# PCB.net
KiCad netlist of a schematic drawn in EAGLE
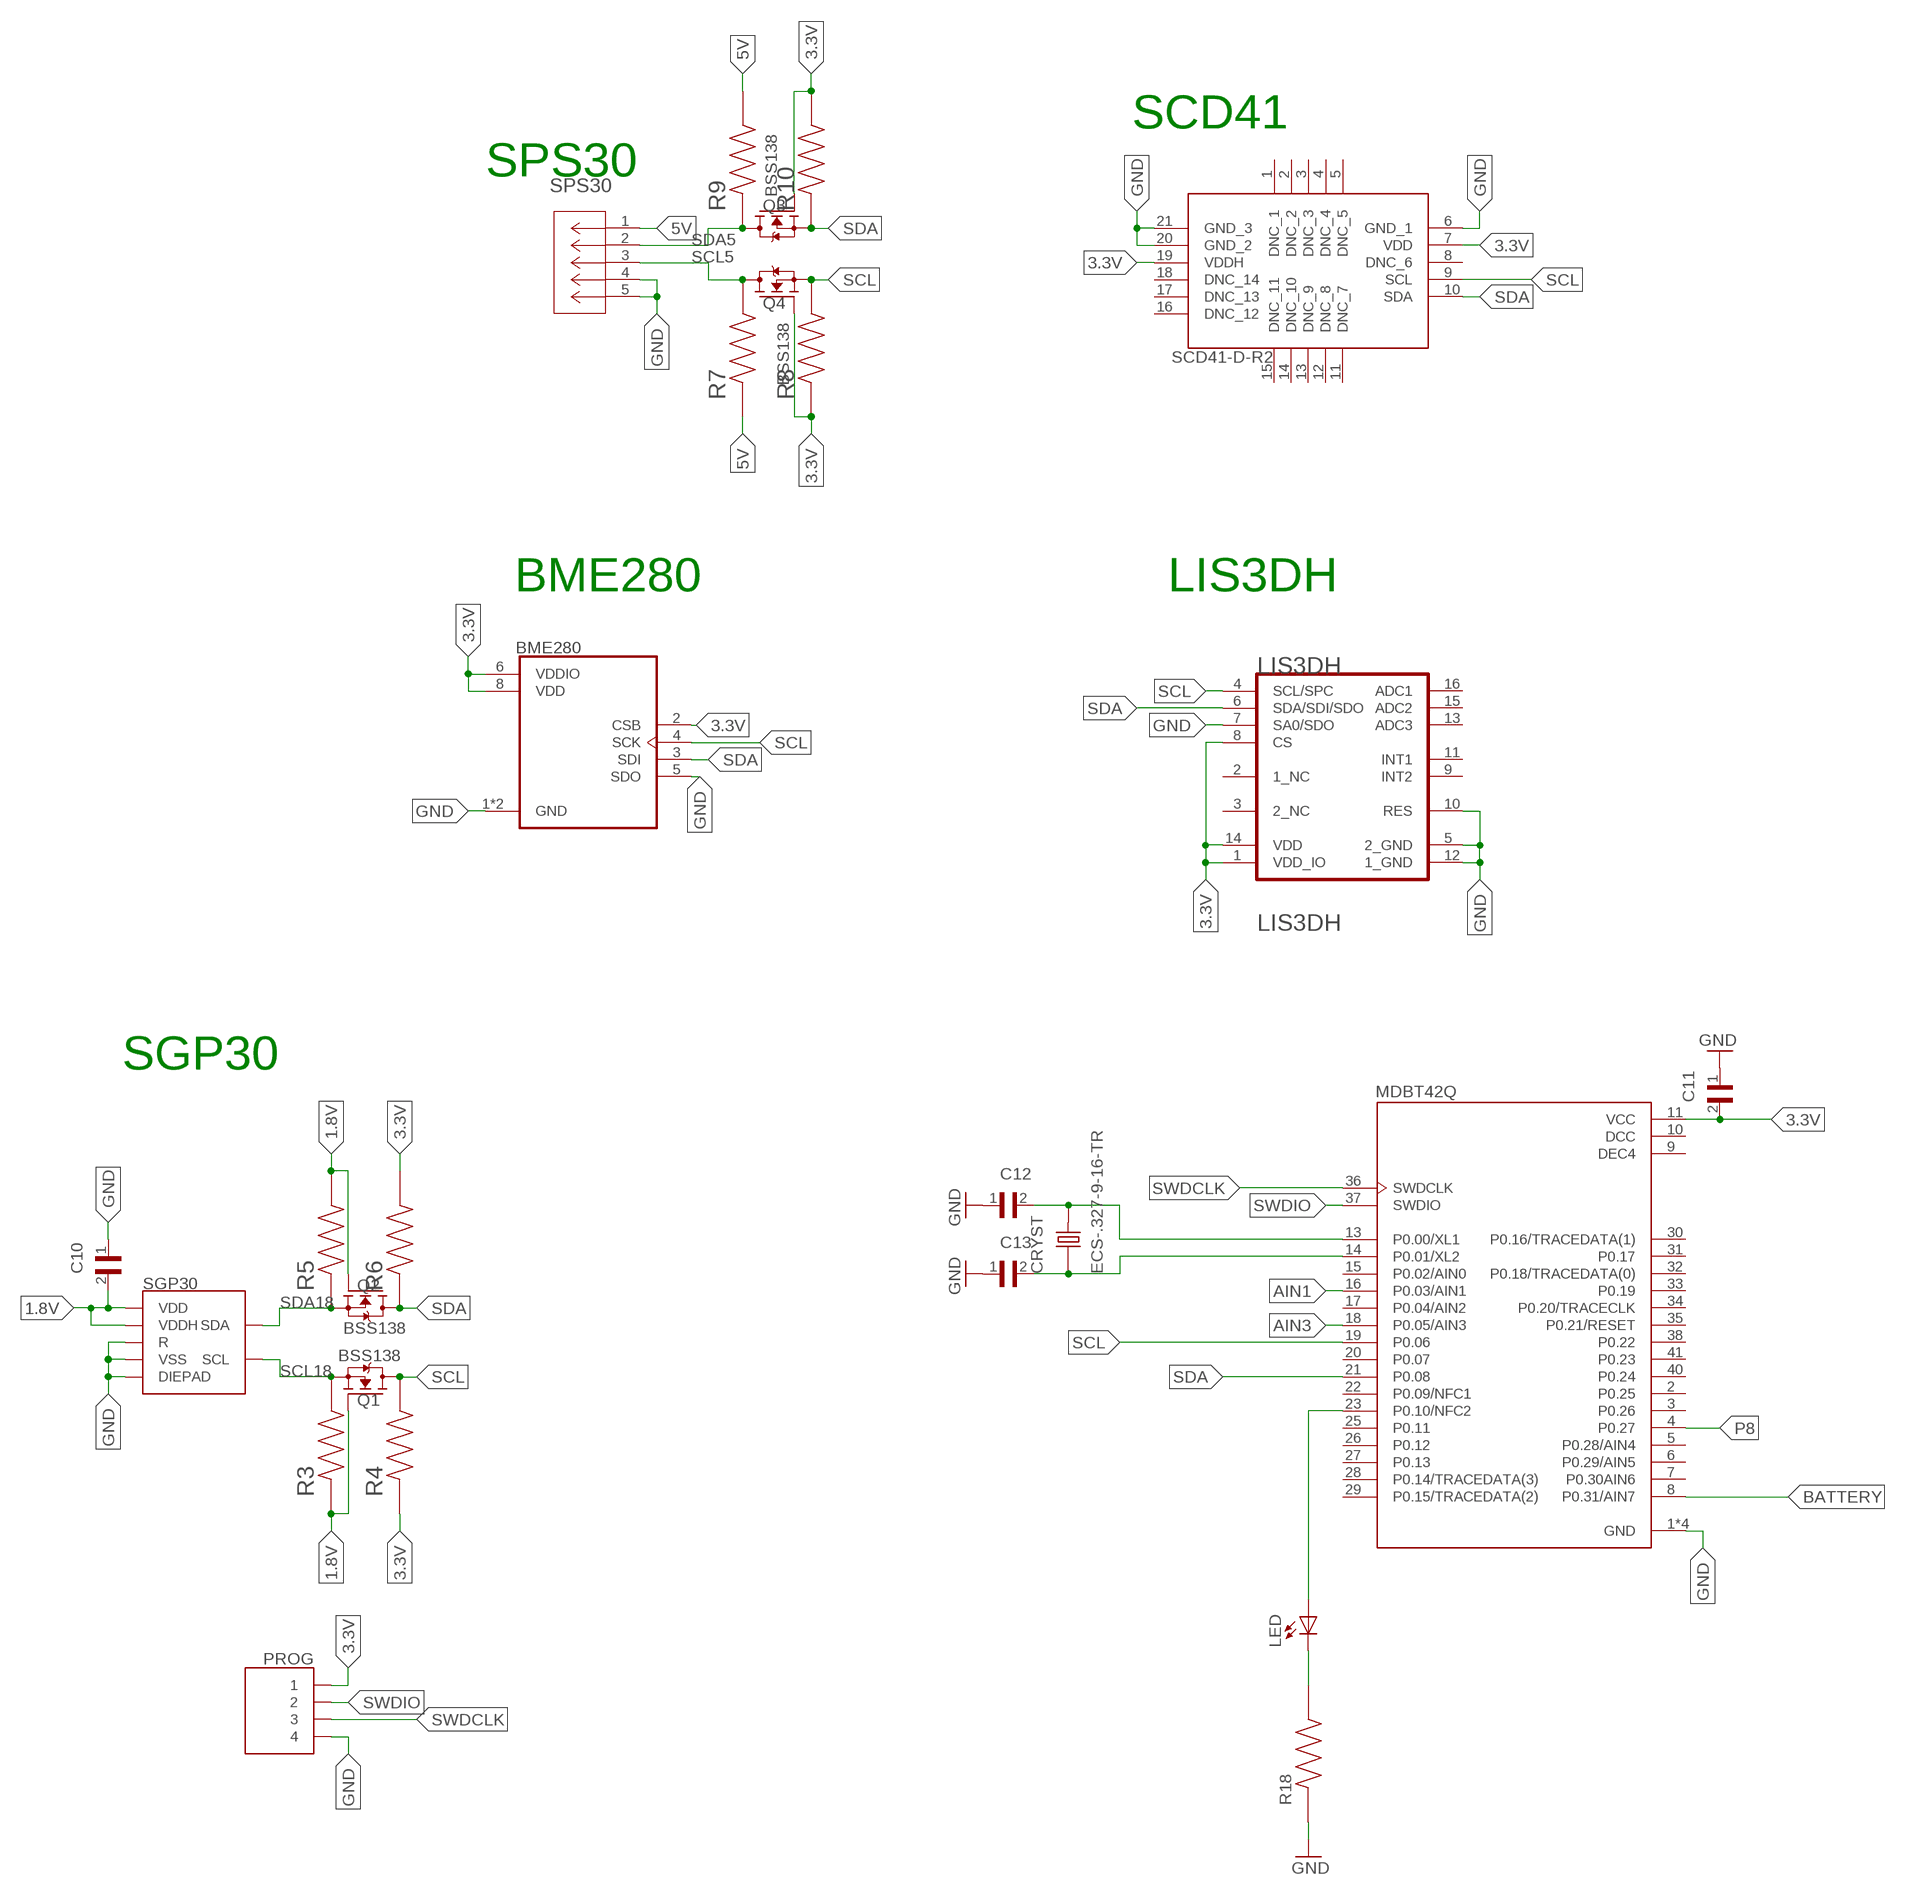
[diagram p0: schematic, sheet 1, part 1 of 2]
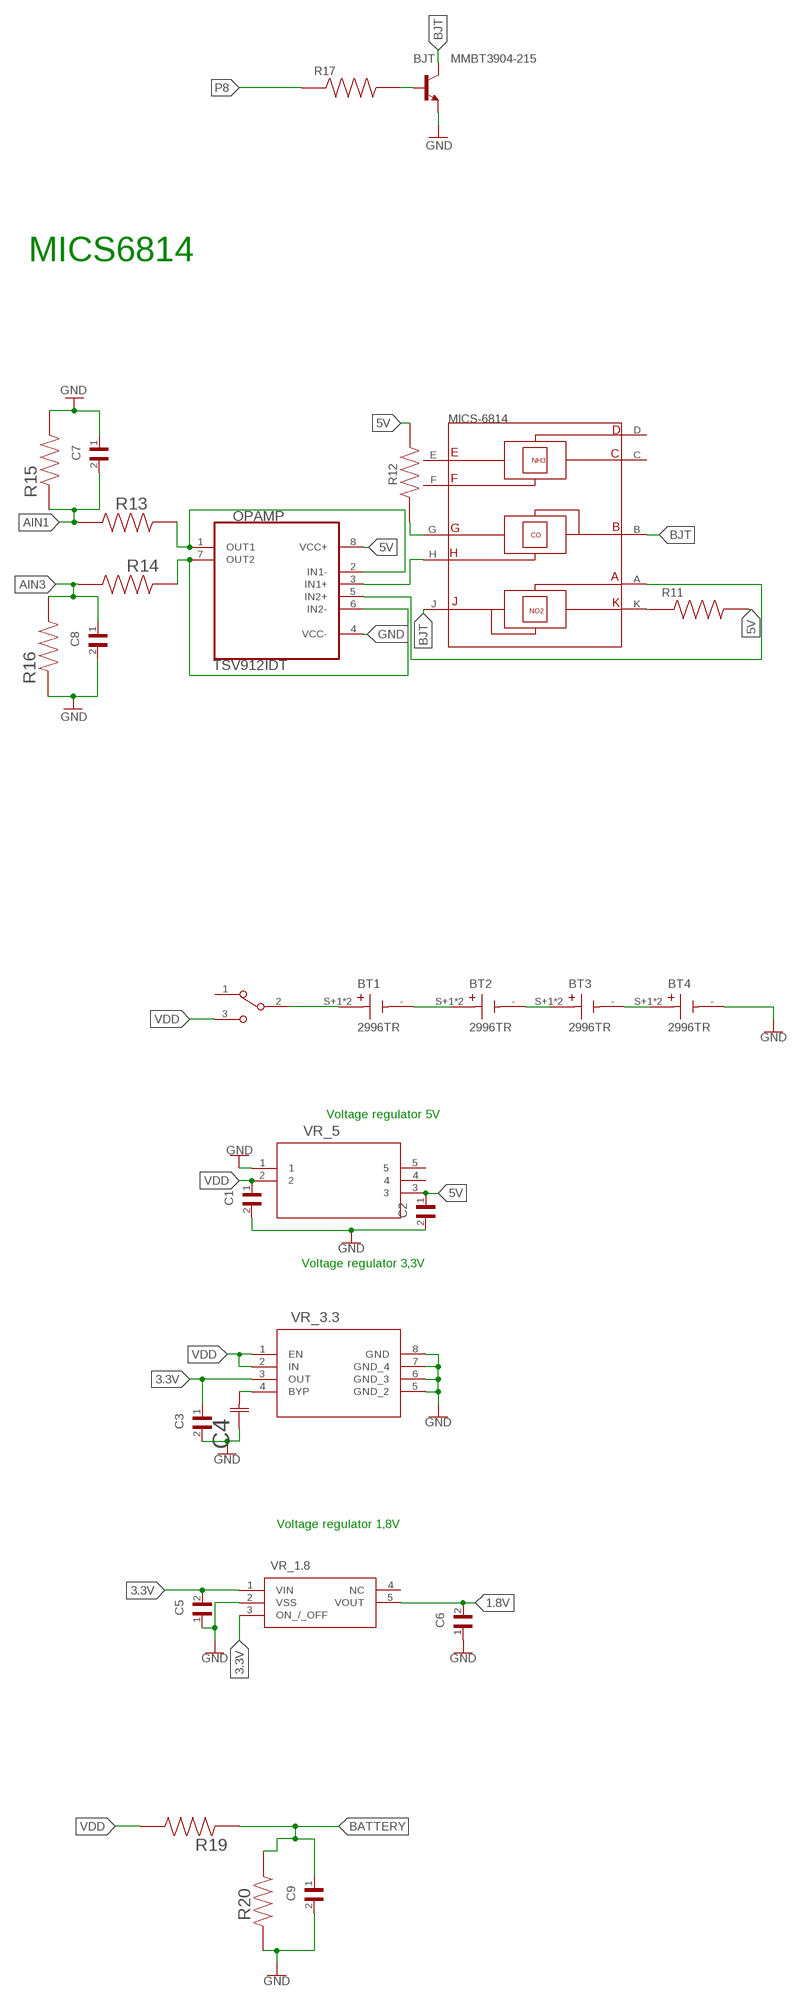
[diagram p1: schematic, sheet 1, part 2 of 2]

(export (version "E")
  (design (tool "Eeschema 10.0.6"))
  (components
    (comp (ref "BJT")
      (value "MMBT3904-215")
      (footprint "eagle-import:SOT95P230X110-3N")
      (fields
        (field (name "DIGI-KEY_PART_NUMBER") "1727-4044-2-ND")
        (field (name "MF") "Nexperia USA")
        (field (name "MP") "MMBT3904,215")
      )
      (libsource (lib "eagle-import") (part "MMBT3904-215"))
    )
    (comp (ref "BME280")
      (value "BME280")
      (footprint "eagle-import:PSON65P250X250X100-8N")
      (fields (field (name "MF") "Bosch"))
      (libsource (lib "eagle-import") (part "BME280"))
    )
    (comp (ref "BT1")
      (value "2996TR")
      (footprint "eagle-import:BAT_2996TR")
      (fields (field (name "DIGI-KEY_PART_NUMBER") "36-2996TR-ND") (field (name "MF") "Keystone Electronics"))
      (libsource (lib "eagle-import") (part "2996TR"))
    )
    (comp (ref "BT2")
      (value "2996TR")
      (footprint "eagle-import:BAT_2996TR")
      (fields (field (name "DIGI-KEY_PART_NUMBER") "36-2996TR-ND") (field (name "MF") "Keystone Electronics"))
      (libsource (lib "eagle-import") (part "2996TR"))
    )
    (comp (ref "BT3")
      (value "2996TR")
      (footprint "eagle-import:BAT_2996TR")
      (fields (field (name "DIGI-KEY_PART_NUMBER") "36-2996TR-ND") (field (name "MF") "Keystone Electronics"))
      (libsource (lib "eagle-import") (part "2996TR"))
    )
    (comp (ref "BT4")
      (value "2996TR")
      (footprint "eagle-import:BAT_2996TR")
      (fields (field (name "DIGI-KEY_PART_NUMBER") "36-2996TR-ND") (field (name "MF") "Keystone Electronics"))
      (libsource (lib "eagle-import") (part "2996TR"))
    )
    (comp (ref "C1")
      (value "C0402C104K9RACAUTO")
      (footprint "eagle-import:CAPC1005X55N")
      (fields (field (name "DIGI-KEY_PART_NUMBER") "399-19367-2-ND") (field (name "MF") "KEMET"))
      (libsource (lib "eagle-import") (part "C0402C104K9RACAUTO"))
    )
    (comp (ref "C2")
      (value "C0402C104K9RACAUTO")
      (footprint "eagle-import:CAPC1005X55N")
      (fields (field (name "DIGI-KEY_PART_NUMBER") "399-19367-2-ND") (field (name "MF") "KEMET"))
      (libsource (lib "eagle-import") (part "C0402C104K9RACAUTO"))
    )
    (comp (ref "C3")
      (value "CL05A225MQ5NNNC")
      (footprint "eagle-import:CAPC1005X55N")
      (fields (field (name "DIGI-KEY_PART_NUMBER") "1276-1469-2-ND") (field (name "MF") "Samsung"))
      (libsource (lib "eagle-import") (part "CL05A225MQ5NNNC"))
    )
    (comp (ref "C4")
      (value "CL05B471KB5NNNCCAP_CL05_SAM")
      (footprint "eagle-import:CAP_CL05_SAM")
      (fields
        (field (name "MANUFACTURER_PART_NUMBER") "CL05B471KB5NNNC")
        (field (name "COPYRIGHT") "Copyright (C) 2022 Ultra Librarian. All rights reserved.")
      )
      (libsource (lib "eagle-import") (part "CL05B471KB5NNNCCAP_CL05_SAM"))
    )
    (comp (ref "C5")
      (value "JMK105BJ105KV-F")
      (footprint "eagle-import:CAPC1005X55N")
      (fields (field (name "DIGI-KEY_PART_NUMBER") "587-1231-2-ND") (field (name "MF") "Taiyo Yuden"))
      (libsource (lib "eagle-import") (part "JMK105BJ105KV-F"))
    )
    (comp (ref "C6")
      (value "JMK105BJ105KV-F")
      (footprint "eagle-import:CAPC1005X55N")
      (fields (field (name "DIGI-KEY_PART_NUMBER") "587-1231-2-ND") (field (name "MF") "Taiyo Yuden"))
      (libsource (lib "eagle-import") (part "JMK105BJ105KV-F"))
    )
    (comp (ref "C7")
      (value "CL05B103KO5NNNC")
      (footprint "eagle-import:CAPC1005X55N")
      (fields
        (field (name "DIGI-KEY_PART_NUMBER") "1276-1051-2-ND")
        (field (name "MF") "Samsung Electro-Mechanics")
      )
      (libsource (lib "eagle-import") (part "CL05B103KO5NNNC"))
    )
    (comp (ref "C8")
      (value "CL05B103KO5NNNC")
      (footprint "eagle-import:CAPC1005X55N")
      (fields
        (field (name "DIGI-KEY_PART_NUMBER") "1276-1051-2-ND")
        (field (name "MF") "Samsung Electro-Mechanics")
      )
      (libsource (lib "eagle-import") (part "CL05B103KO5NNNC"))
    )
    (comp (ref "C9")
      (value "CL05B103KO5NNNC")
      (footprint "eagle-import:CAPC1005X55N")
      (fields
        (field (name "DIGI-KEY_PART_NUMBER") "1276-1051-2-ND")
        (field (name "MF") "Samsung Electro-Mechanics")
      )
      (libsource (lib "eagle-import") (part "CL05B103KO5NNNC"))
    )
    (comp (ref "C10")
      (value "C0402C104K9RACAUTO")
      (footprint "eagle-import:CAPC1005X55N")
      (fields (field (name "DIGI-KEY_PART_NUMBER") "399-19367-2-ND") (field (name "MF") "KEMET"))
      (libsource (lib "eagle-import") (part "C0402C104K9RACAUTO"))
    )
    (comp (ref "C11")
      (value "CL05A106MP5NUNC")
      (footprint "eagle-import:CAPC1005X55N")
      (fields (field (name "DIGI-KEY_PART_NUMBER") "1276-1450-2-ND") (field (name "MF") "Samsung"))
      (libsource (lib "eagle-import") (part "CL05A106MP5NUNC"))
    )
    (comp (ref "C12")
      (value "04025A120FAT2A")
      (footprint "eagle-import:CAPC1005X56N")
      (fields (field (name "DIGI-KEY_PART_NUMBER") "478-10087-2-ND") (field (name "MF") "AVX"))
      (libsource (lib "eagle-import") (part "04025A120FAT2A"))
    )
    (comp (ref "C13")
      (value "04025A120FAT2A")
      (footprint "eagle-import:CAPC1005X56N")
      (fields (field (name "DIGI-KEY_PART_NUMBER") "478-10087-2-ND") (field (name "MF") "AVX"))
      (libsource (lib "eagle-import") (part "04025A120FAT2A"))
    )
    (comp (ref "CRYST")
      (value "ECS-.327-9-16-TR")
      (footprint "eagle-import:XTAL_ECS-.327-9-16-TR")
      (fields (field (name "DIGI-KEY_PART_NUMBER") "XC2132TR-ND") (field (name "MF") "ECS Inc."))
      (libsource (lib "eagle-import") (part "ECS-.327-9-16-TR"))
    )
    (comp (ref "LED")
      (value "LTST-C170KRKT")
      (footprint "eagle-import:DIOC200X125X110")
      (fields (field (name "DIGI-KEY_PART_NUMBER") "160-1415-2-ND") (field (name "MF") "Lite-On Inc."))
      (libsource (lib "eagle-import") (part "LTST-C170KRKT"))
    )
    (comp (ref "LIS3DH")
      (value "STMICROELECTRONICS_LIS3DHSTMICROELECTRONICS_LIS3DH_0_0")
      (footprint "eagle-import:STMICROELECTRONICS_LIS3DH_0")
      (fields (field (name "MF") "STMicroelectronics") (field (name "MPN") "LIS3DH"))
      (libsource (lib "eagle-import") (part "STMICROELECTRONICS_LIS3DHSTMICROELECTRONICS_LIS3DH_0_0"))
    )
    (comp (ref "MDBT42Q")
      (value "317030213")
      (footprint "eagle-import:XCVR_317030213")
      (fields (field (name "DIGI-KEY_PART_NUMBER") "1597-1434-ND") (field (name "MF") "Seeed Technology"))
      (libsource (lib "eagle-import") (part "317030213"))
    )
    (comp (ref "MICS6814")
      (value "MICS-6814")
      (footprint "eagle-import:SENSOR_MICS-6814")
      (fields (field (name "MF") "MikroElektronika"))
      (libsource (lib "eagle-import") (part "MICS-6814"))
    )
    (comp (ref "OPAMP")
      (value "TSV912IDT")
      (footprint "eagle-import:SOIC127P600X175-8N")
      (fields (field (name "MF") "STMicroelectronics"))
      (libsource (lib "eagle-import") (part "TSV912IDT"))
    )
    (comp (ref "PROG")
      (value "BG306-04-A-1-0400-X-X_REVD")
      (footprint "eagle-import:GCT_BG306-04-A-1-0400-X-X_REVD")
      (fields
        (field (name "DIGI-KEY_PART_NUMBER") "2073-BG306-04-A-1-0400-L-BTR-ND")
        (field (name "MF") "Global Connector Technology")
        (field (name "MP") "BG306-04-A-1-0400-L-B")
      )
      (libsource (lib "eagle-import") (part "BG306-04-A-1-0400-X-X_REVD"))
    )
    (comp (ref "Q1")
      (value "BSS138")
      (footprint "eagle-import:SOT95P240X111-3N")
      (fields (field (name "DIGI-KEY_PART_NUMBER") "BSS138TR-ND") (field (name "MF") "ON Semiconductor"))
      (libsource (lib "eagle-import") (part "BSS138"))
    )
    (comp (ref "Q2")
      (value "BSS138")
      (footprint "eagle-import:SOT95P240X111-3N")
      (fields (field (name "DIGI-KEY_PART_NUMBER") "BSS138TR-ND") (field (name "MF") "ON Semiconductor"))
      (libsource (lib "eagle-import") (part "BSS138"))
    )
    (comp (ref "Q3")
      (value "BSS138")
      (footprint "eagle-import:SOT95P240X111-3N")
      (fields (field (name "DIGI-KEY_PART_NUMBER") "BSS138TR-ND") (field (name "MF") "ON Semiconductor"))
      (libsource (lib "eagle-import") (part "BSS138"))
    )
    (comp (ref "Q4")
      (value "BSS138")
      (footprint "eagle-import:SOT95P240X111-3N")
      (fields (field (name "DIGI-KEY_PART_NUMBER") "BSS138TR-ND") (field (name "MF") "ON Semiconductor"))
      (libsource (lib "eagle-import") (part "BSS138"))
    )
    (comp (ref "R3")
      (value "MCS0402MC1002FE000")
      (footprint "eagle-import:RESC1005X37N")
      (fields
        (field (name "DIGI-KEY_PART_NUMBER") "MCS0402-10.0K-MFTR-ND")
        (field (name "MF") "Vishay Beyschlag")
      )
      (libsource (lib "eagle-import") (part "MCS0402MC1002FE000"))
    )
    (comp (ref "R4")
      (value "MCS0402MC1002FE000")
      (footprint "eagle-import:RESC1005X37N")
      (fields
        (field (name "DIGI-KEY_PART_NUMBER") "MCS0402-10.0K-MFTR-ND")
        (field (name "MF") "Vishay Beyschlag")
      )
      (libsource (lib "eagle-import") (part "MCS0402MC1002FE000"))
    )
    (comp (ref "R5")
      (value "MCS0402MC1002FE000")
      (footprint "eagle-import:RESC1005X37N")
      (fields
        (field (name "DIGI-KEY_PART_NUMBER") "MCS0402-10.0K-MFTR-ND")
        (field (name "MF") "Vishay Beyschlag")
      )
      (libsource (lib "eagle-import") (part "MCS0402MC1002FE000"))
    )
    (comp (ref "R6")
      (value "MCS0402MC1002FE000")
      (footprint "eagle-import:RESC1005X37N")
      (fields
        (field (name "DIGI-KEY_PART_NUMBER") "MCS0402-10.0K-MFTR-ND")
        (field (name "MF") "Vishay Beyschlag")
      )
      (libsource (lib "eagle-import") (part "MCS0402MC1002FE000"))
    )
    (comp (ref "R7")
      (value "MCS0402MC1002FE000")
      (footprint "eagle-import:RESC1005X37N")
      (fields
        (field (name "DIGI-KEY_PART_NUMBER") "MCS0402-10.0K-MFTR-ND")
        (field (name "MF") "Vishay Beyschlag")
      )
      (libsource (lib "eagle-import") (part "MCS0402MC1002FE000"))
    )
    (comp (ref "R8")
      (value "MCS0402MC1002FE000")
      (footprint "eagle-import:RESC1005X37N")
      (fields
        (field (name "DIGI-KEY_PART_NUMBER") "MCS0402-10.0K-MFTR-ND")
        (field (name "MF") "Vishay Beyschlag")
      )
      (libsource (lib "eagle-import") (part "MCS0402MC1002FE000"))
    )
    (comp (ref "R9")
      (value "MCS0402MC1002FE000")
      (footprint "eagle-import:RESC1005X37N")
      (fields
        (field (name "DIGI-KEY_PART_NUMBER") "MCS0402-10.0K-MFTR-ND")
        (field (name "MF") "Vishay Beyschlag")
      )
      (libsource (lib "eagle-import") (part "MCS0402MC1002FE000"))
    )
    (comp (ref "R10")
      (value "MCS0402MC1002FE000")
      (footprint "eagle-import:RESC1005X37N")
      (fields
        (field (name "DIGI-KEY_PART_NUMBER") "MCS0402-10.0K-MFTR-ND")
        (field (name "MF") "Vishay Beyschlag")
      )
      (libsource (lib "eagle-import") (part "MCS0402MC1002FE000"))
    )
    (comp (ref "R11")
      (value "ERJPA2F1300X")
      (footprint "eagle-import:RES_ERJPA2F1300X")
      (fields (field (name "DIGI-KEY_PART_NUMBER") "P124437TR-ND") (field (name "MF") "Panasonic"))
      (libsource (lib "eagle-import") (part "ERJPA2F1300X"))
    )
    (comp (ref "R12")
      (value "ERJPA2J821X")
      (footprint "eagle-import:RES_ERJPA2J821X")
      (fields (field (name "DIGI-KEY_PART_NUMBER") "P124598TR-ND") (field (name "MF") "Panasonic"))
      (libsource (lib "eagle-import") (part "ERJPA2J821X"))
    )
    (comp (ref "R13")
      (value "ERJ-2GEJ515X")
      (footprint "eagle-import:RESC1005X40N")
      (fields (field (name "DIGI-KEY_PART_NUMBER") "P5.1MJTR-ND") (field (name "MF") "Panasonic"))
      (libsource (lib "eagle-import") (part "ERJ-2GEJ515X"))
    )
    (comp (ref "R14")
      (value "ERJ-2GEJ515X")
      (footprint "eagle-import:RESC1005X40N")
      (fields (field (name "DIGI-KEY_PART_NUMBER") "P5.1MJTR-ND") (field (name "MF") "Panasonic"))
      (libsource (lib "eagle-import") (part "ERJ-2GEJ515X"))
    )
    (comp (ref "R15")
      (value "ERJ-2GEJ106X")
      (footprint "eagle-import:RESC1005X40N")
      (fields (field (name "DIGI-KEY_PART_NUMBER") "P10MJTR-ND") (field (name "MF") "Panasonic Electronic"))
      (libsource (lib "eagle-import") (part "ERJ-2GEJ106X"))
    )
    (comp (ref "R16")
      (value "ERJ-2GEJ106X")
      (footprint "eagle-import:RESC1005X40N")
      (fields (field (name "DIGI-KEY_PART_NUMBER") "P10MJTR-ND") (field (name "MF") "Panasonic Electronic"))
      (libsource (lib "eagle-import") (part "ERJ-2GEJ106X"))
    )
    (comp (ref "R17")
      (value "ERJPA2F5101X")
      (footprint "eagle-import:RES_ERJPA2F5101X")
      (fields (field (name "DIGI-KEY_PART_NUMBER") "P124488TR-ND") (field (name "MF") "Panasonic"))
      (libsource (lib "eagle-import") (part "ERJPA2F5101X"))
    )
    (comp (ref "R18")
      (value "ERA2AEB331X")
      (footprint "eagle-import:RES_ERA2AEB331X")
      (fields (field (name "DIGI-KEY_PART_NUMBER") "P330DCTR-ND") (field (name "MF") "Panasonic"))
      (libsource (lib "eagle-import") (part "ERA2AEB331X"))
    )
    (comp (ref "R19")
      (value "ERJ-2GEJ106X")
      (footprint "eagle-import:RESC1005X40N")
      (fields (field (name "DIGI-KEY_PART_NUMBER") "P10MJTR-ND") (field (name "MF") "Panasonic Electronic"))
      (libsource (lib "eagle-import") (part "ERJ-2GEJ106X"))
    )
    (comp (ref "R20")
      (value "ERJ-2GEJ106X")
      (footprint "eagle-import:RESC1005X40N")
      (fields (field (name "DIGI-KEY_PART_NUMBER") "P10MJTR-ND") (field (name "MF") "Panasonic Electronic"))
      (libsource (lib "eagle-import") (part "ERJ-2GEJ106X"))
    )
    (comp (ref "S1")
      (value "EG1213")
      (footprint "eagle-import:SW_EG1213")
      (fields (field (name "DIGI-KEY_PART_NUMBER") "EG1906-ND") (field (name "MF") "E-Switch"))
      (libsource (lib "eagle-import") (part "EG1213"))
    )
    (comp (ref "SCD41")
      (value "SCD41-D-R2")
      (footprint "eagle-import:SCD41DR2")
      (fields (field (name "MOUSER_PART_NUMBER") "403-SCD41-D-R2"))
      (libsource (lib "eagle-import") (part "SCD41-D-R2"))
    )
    (comp (ref "SGP30")
      (value "SGP30")
      (footprint "eagle-import:SGP30")
      (fields (field (name "MF") "Sensirion AG"))
      (libsource (lib "eagle-import") (part "SGP30"))
    )
    (comp (ref "SPS30")
      (value "S5B-ZR-SM4A-TF_(LF)_(SN)CONN_S5B-ZR-SM4A-TF_JST")
      (footprint "eagle-import:CONN_S5B-ZR-SM4A-TF_JST")
      (fields
        (field (name "MANUFACTURER_PART_NUMBER") "S5B-ZR-SM4A-TF (LF) (SN)")
        (field (name "COPYRIGHT") "Copyright (C) 2022 Ultra Librarian. All rights reserved.")
      )
      (libsource (lib "eagle-import") (part "S5B-ZR-SM4A-TF_(LF)_(SN)CONN_S5B-ZR-SM4A-TF_JST"))
    )
    (comp (ref "VR_1.8")
      (value "S-1318D18-M5T1U4")
      (footprint "eagle-import:SOT95P275X130-5N")
      (fields (field (name "MOUSER_PART_NUMBER") "628-S-1318D18-M5T1U4"))
      (libsource (lib "eagle-import") (part "S-1318D18-M5T1U4"))
    )
    (comp (ref "VR_3.3")
      (value "MIC5219-3.3YMMMSOP-8LD-PL-1_MCH")
      (footprint "eagle-import:MSOP-8LD-PL-1_MCH")
      (fields
        (field (name "MANUFACTURER_PART_NUMBER") "MIC5219-3.3YMM")
        (field (name "COPYRIGHT") "Copyright (C) 2022 Ultra Librarian. All rights reserved.")
      )
      (libsource (lib "eagle-import") (part "MIC5219-3.3YMMMSOP-8LD-PL-1_MCH"))
    )
    (comp (ref "VR_5")
      (value "MC78LC50NTRGTSOT23-5_ONS")
      (footprint "eagle-import:TSOT23-5_ONS")
      (fields
        (field (name "MANUFACTURER_PART_NUMBER") "MC78LC50NTRG")
        (field (name "COPYRIGHT") "Copyright (C) 2022 Ultra Librarian. All rights reserved.")
      )
      (libsource (lib "eagle-import") (part "MC78LC50NTRGTSOT23-5_ONS"))
    )
  )
  (nets
    (net (code "1") (name "/DCC") (class "Default")
      (node (ref "MDBT42Q") (pin "10") (pinfunction "DCC_10") (pintype "power_in"))
    )
    (net (code "2") (name "/DEC4") (class "Default")
      (node (ref "MDBT42Q") (pin "9") (pinfunction "DEC4_9") (pintype "power_in"))
    )
    (net (code "3") (name "/SCL5") (class "Default")
      (node (ref "Q4") (pin "3") (pinfunction "D_3") (pintype "passive"))
      (node (ref "R7") (pin "2") (pinfunction "2_2") (pintype "passive"))
      (node (ref "SPS30") (pin "3") (pinfunction "3_3") (pintype "passive"))
    )
    (net (code "4") (name "/SCL18") (class "Default")
      (node (ref "Q1") (pin "2") (pinfunction "S_2") (pintype "passive"))
      (node (ref "R3") (pin "2") (pinfunction "2_2") (pintype "passive"))
      (node (ref "SGP30") (pin "6") (pinfunction "SCL_6") (pintype "bidirectional"))
    )
    (net (code "5") (name "/SDA5") (class "Default")
      (node (ref "Q3") (pin "3") (pinfunction "D_3") (pintype "passive"))
      (node (ref "R9") (pin "1") (pinfunction "1_1") (pintype "passive"))
      (node (ref "SPS30") (pin "2") (pinfunction "2_2") (pintype "passive"))
    )
    (net (code "6") (name "/SDA18") (class "Default")
      (node (ref "Q2") (pin "2") (pinfunction "S_2") (pintype "passive"))
      (node (ref "R5") (pin "1") (pinfunction "1_1") (pintype "passive"))
      (node (ref "SGP30") (pin "3") (pinfunction "SDA_3") (pintype "bidirectional"))
    )
    (net (code "7") (name "1.8V") (class "Default")
      (node (ref "C10") (pin "2") (pinfunction "2_2") (pintype "passive"))
      (node (ref "C6") (pin "2") (pinfunction "2_2") (pintype "passive"))
      (node (ref "Q1") (pin "1") (pinfunction "G_1") (pintype "passive"))
      (node (ref "Q2") (pin "1") (pinfunction "G_1") (pintype "passive"))
      (node (ref "R3") (pin "1") (pinfunction "1_1") (pintype "passive"))
      (node (ref "R5") (pin "2") (pinfunction "2_2") (pintype "passive"))
      (node (ref "SGP30") (pin "1") (pinfunction "VDD_1") (pintype "bidirectional"))
      (node (ref "SGP30") (pin "5") (pinfunction "VDDH_5") (pintype "bidirectional"))
      (node (ref "VR_1.8") (pin "5") (pinfunction "VOUT_5") (pintype "bidirectional"))
    )
    (net (code "8") (name "3.3V") (class "Default")
      (node (ref "BME280") (pin "2") (pinfunction "CSB_2") (pintype "input"))
      (node (ref "BME280") (pin "6") (pinfunction "VDDIO_6") (pintype "power_in"))
      (node (ref "BME280") (pin "8") (pinfunction "VDD_8") (pintype "power_in"))
      (node (ref "C11") (pin "2") (pinfunction "2_2") (pintype "passive"))
      (node (ref "C3") (pin "1") (pinfunction "1_1") (pintype "passive"))
      (node (ref "C5") (pin "2") (pinfunction "2_2") (pintype "passive"))
      (node (ref "LIS3DH") (pin "1") (pinfunction "VDD_IO_1") (pintype "power_in"))
      (node (ref "LIS3DH") (pin "14") (pinfunction "VDD_14") (pintype "power_in"))
      (node (ref "LIS3DH") (pin "8") (pinfunction "CS_8") (pintype "input"))
      (node (ref "MDBT42Q") (pin "11") (pinfunction "VCC_11") (pintype "power_in"))
      (node (ref "PROG") (pin "1") (pinfunction "1_1") (pintype "passive"))
      (node (ref "Q3") (pin "1") (pinfunction "G_1") (pintype "passive"))
      (node (ref "Q4") (pin "1") (pinfunction "G_1") (pintype "passive"))
      (node (ref "R10") (pin "2") (pinfunction "2_2") (pintype "passive"))
      (node (ref "R4") (pin "1") (pinfunction "1_1") (pintype "passive"))
      (node (ref "R6") (pin "2") (pinfunction "2_2") (pintype "passive"))
      (node (ref "R8") (pin "1") (pinfunction "1_1") (pintype "passive"))
      (node (ref "SCD41") (pin "19") (pinfunction "VDDH_19") (pintype "bidirectional"))
      (node (ref "SCD41") (pin "7") (pinfunction "VDD_7") (pintype "bidirectional"))
      (node (ref "VR_1.8") (pin "1") (pinfunction "VIN_1") (pintype "bidirectional"))
      (node (ref "VR_1.8") (pin "3") (pinfunction "ON_/_OFF_3") (pintype "bidirectional"))
      (node (ref "VR_3.3") (pin "3") (pinfunction "OUT_3") (pintype "output"))
    )
    (net (code "9") (name "5V") (class "Default")
      (node (ref "C2") (pin "1") (pinfunction "1_1") (pintype "passive"))
      (node (ref "OPAMP") (pin "8") (pinfunction "VCC+_8") (pintype "power_in"))
      (node (ref "R11") (pin "2") (pinfunction "2_2") (pintype "passive"))
      (node (ref "R12") (pin "2") (pinfunction "2_2") (pintype "passive"))
      (node (ref "R7") (pin "1") (pinfunction "1_1") (pintype "passive"))
      (node (ref "R9") (pin "2") (pinfunction "2_2") (pintype "passive"))
      (node (ref "SPS30") (pin "1") (pinfunction "1_1") (pintype "passive"))
      (node (ref "VR_5") (pin "3") (pinfunction "3_3") (pintype "passive"))
    )
    (net (code "10") (name "AIN1") (class "Default")
      (node (ref "C7") (pin "2") (pinfunction "2_2") (pintype "passive"))
      (node (ref "MDBT42Q") (pin "16") (pinfunction "P0.03/AIN1_16") (pintype "bidirectional"))
      (node (ref "R13") (pin "1") (pinfunction "1_1") (pintype "passive"))
      (node (ref "R15") (pin "1") (pinfunction "1_1") (pintype "passive"))
    )
    (net (code "11") (name "AIN3") (class "Default")
      (node (ref "C8") (pin "1") (pinfunction "1_1") (pintype "passive"))
      (node (ref "MDBT42Q") (pin "18") (pinfunction "P0.05/AIN3_18") (pintype "bidirectional"))
      (node (ref "R14") (pin "1") (pinfunction "1_1") (pintype "passive"))
      (node (ref "R16") (pin "2") (pinfunction "2_2") (pintype "passive"))
    )
    (net (code "12") (name "BATTERY") (class "Default")
      (node (ref "C9") (pin "1") (pinfunction "1_1") (pintype "passive"))
      (node (ref "MDBT42Q") (pin "8") (pinfunction "P0.31/AIN7_8") (pintype "bidirectional"))
      (node (ref "R19") (pin "1") (pinfunction "1_1") (pintype "passive"))
      (node (ref "R20") (pin "1") (pinfunction "1_1") (pintype "passive"))
    )
    (net (code "13") (name "BJT") (class "Default")
      (node (ref "BJT") (pin "3") (pinfunction "C_3") (pintype "passive"))
      (node (ref "MICS6814") (pin "B") (pinfunction "RH1/RS1_RED_B") (pintype "passive"))
      (node (ref "MICS6814") (pin "J") (pinfunction "RH1/RS1_OX_J") (pintype "passive"))
    )
    (net (code "14") (name "GND") (class "Default")
      (node (ref "BJT") (pin "2") (pinfunction "E_2") (pintype "passive"))
      (node (ref "BME280") (pin "1") (pinfunction "GND_1") (pintype "power_in"))
      (node (ref "BME280") (pin "5") (pinfunction "SDO_5") (pintype "bidirectional"))
      (node (ref "BME280") (pin "7") (pinfunction "GND_7") (pintype "power_in"))
      (node (ref "BT4") (pin "-") (pinfunction "-_-") (pintype "passive"))
      (node (ref "C1") (pin "2") (pinfunction "2_2") (pintype "passive"))
      (node (ref "C10") (pin "1") (pinfunction "1_1") (pintype "passive"))
      (node (ref "C11") (pin "1") (pinfunction "1_1") (pintype "passive"))
      (node (ref "C12") (pin "1") (pinfunction "1_1") (pintype "passive"))
      (node (ref "C13") (pin "1") (pinfunction "1_1") (pintype "passive"))
      (node (ref "C2") (pin "2") (pinfunction "2_2") (pintype "passive"))
      (node (ref "C3") (pin "2") (pinfunction "2_2") (pintype "passive"))
      (node (ref "C4") (pin "1") (pinfunction "1_1") (pintype "passive"))
      (node (ref "C5") (pin "1") (pinfunction "1_1") (pintype "passive"))
      (node (ref "C6") (pin "1") (pinfunction "1_1") (pintype "passive"))
      (node (ref "C7") (pin "1") (pinfunction "1_1") (pintype "passive"))
      (node (ref "C8") (pin "2") (pinfunction "2_2") (pintype "passive"))
      (node (ref "C9") (pin "2") (pinfunction "2_2") (pintype "passive"))
      (node (ref "LIS3DH") (pin "10") (pinfunction "RES_10") (pintype "power_in"))
      (node (ref "LIS3DH") (pin "12") (pinfunction "1_GND_12") (pintype "power_in"))
      (node (ref "LIS3DH") (pin "5") (pinfunction "2_GND_5") (pintype "power_in"))
      (node (ref "LIS3DH") (pin "7") (pinfunction "SA0/SDO_7") (pintype "bidirectional"))
      (node (ref "MDBT42Q") (pin "1") (pinfunction "GND_1") (pintype "power_in"))
      (node (ref "MDBT42Q") (pin "12") (pinfunction "GND_12") (pintype "power_in"))
      (node (ref "MDBT42Q") (pin "24") (pinfunction "GND_24") (pintype "power_in"))
      (node (ref "MDBT42Q") (pin "39") (pinfunction "GND_39") (pintype "power_in"))
      (node (ref "OPAMP") (pin "4") (pinfunction "VCC-_4") (pintype "power_in"))
      (node (ref "PROG") (pin "4") (pinfunction "4_4") (pintype "passive"))
      (node (ref "R15") (pin "2") (pinfunction "2_2") (pintype "passive"))
      (node (ref "R16") (pin "1") (pinfunction "1_1") (pintype "passive"))
      (node (ref "R18") (pin "1") (pinfunction "1_1") (pintype "passive"))
      (node (ref "R20") (pin "2") (pinfunction "2_2") (pintype "passive"))
      (node (ref "SCD41") (pin "20") (pinfunction "GND_2_20") (pintype "bidirectional"))
      (node (ref "SCD41") (pin "21") (pinfunction "GND_3_21") (pintype "bidirectional"))
      (node (ref "SCD41") (pin "6") (pinfunction "GND_1_6") (pintype "bidirectional"))
      (node (ref "SGP30") (pin "2") (pinfunction "VSS_2") (pintype "bidirectional"))
      (node (ref "SGP30") (pin "4") (pinfunction "R_4") (pintype "bidirectional"))
      (node (ref "SGP30") (pin "DIEPAD") (pinfunction "DIEPAD_DIEPAD") (pintype "bidirectional"))
      (node (ref "SPS30") (pin "4") (pinfunction "4_4") (pintype "passive"))
      (node (ref "SPS30") (pin "5") (pinfunction "5_5") (pintype "passive"))
      (node (ref "VR_1.8") (pin "2") (pinfunction "VSS_2") (pintype "bidirectional"))
      (node (ref "VR_3.3") (pin "5") (pinfunction "GND_2_5") (pintype "passive"))
      (node (ref "VR_3.3") (pin "6") (pinfunction "GND_3_6") (pintype "passive"))
      (node (ref "VR_3.3") (pin "7") (pinfunction "GND_4_7") (pintype "passive"))
      (node (ref "VR_3.3") (pin "8") (pinfunction "GND_8") (pintype "passive"))
      (node (ref "VR_5") (pin "1") (pinfunction "1_1") (pintype "passive"))
    )
    (net (code "15") (name "Net-(BJT-B)") (class "Default")
      (node (ref "BJT") (pin "1") (pinfunction "B_1") (pintype "passive"))
      (node (ref "R17") (pin "2") (pinfunction "2_2") (pintype "passive"))
    )
    (net (code "16") (name "Net-(BT1-+-PadS+1)") (class "Default")
      (node (ref "BT1") (pin "S+1") (pinfunction "+_S+1") (pintype "passive"))
      (node (ref "BT1") (pin "S+2") (pinfunction "+_S+2") (pintype "passive"))
      (node (ref "S1") (pin "2") (pinfunction "2_2") (pintype "passive"))
    )
    (net (code "17") (name "Net-(BT1-Pad-)") (class "Default")
      (node (ref "BT1") (pin "-") (pinfunction "-_-") (pintype "passive"))
      (node (ref "BT2") (pin "S+1") (pinfunction "+_S+1") (pintype "passive"))
      (node (ref "BT2") (pin "S+2") (pinfunction "+_S+2") (pintype "passive"))
    )
    (net (code "18") (name "Net-(BT2-Pad-)") (class "Default")
      (node (ref "BT2") (pin "-") (pinfunction "-_-") (pintype "passive"))
      (node (ref "BT3") (pin "S+1") (pinfunction "+_S+1") (pintype "passive"))
      (node (ref "BT3") (pin "S+2") (pinfunction "+_S+2") (pintype "passive"))
    )
    (net (code "19") (name "Net-(BT3-Pad-)") (class "Default")
      (node (ref "BT3") (pin "-") (pinfunction "-_-") (pintype "passive"))
      (node (ref "BT4") (pin "S+1") (pinfunction "+_S+1") (pintype "passive"))
      (node (ref "BT4") (pin "S+2") (pinfunction "+_S+2") (pintype "passive"))
    )
    (net (code "20") (name "Net-(LED-Pad-)") (class "Default")
      (node (ref "LED") (pin "-") (pinfunction "-_-") (pintype "passive"))
      (node (ref "R18") (pin "2") (pinfunction "2_2") (pintype "passive"))
    )
    (net (code "21") (name "Net-(MDBT42Q-P0.00{slash}XL1)") (class "Default")
      (node (ref "C12") (pin "2") (pinfunction "2_2") (pintype "passive"))
      (node (ref "CRYST") (pin "2") (pinfunction "2_2") (pintype "passive"))
      (node (ref "MDBT42Q") (pin "13") (pinfunction "P0.00/XL1_13") (pintype "bidirectional"))
    )
    (net (code "22") (name "Net-(MDBT42Q-P0.01{slash}XL2)") (class "Default")
      (node (ref "C13") (pin "2") (pinfunction "2_2") (pintype "passive"))
      (node (ref "CRYST") (pin "1") (pinfunction "1_1") (pintype "passive"))
      (node (ref "MDBT42Q") (pin "14") (pinfunction "P0.01/XL2_14") (pintype "bidirectional"))
    )
    (net (code "23") (name "Net-(MDBT42Q-P0.10{slash}NFC2)") (class "Default")
      (node (ref "LED") (pin "+") (pinfunction "+_+") (pintype "passive"))
      (node (ref "MDBT42Q") (pin "23") (pinfunction "P0.10/NFC2_23") (pintype "bidirectional"))
    )
    (net (code "24") (name "Net-(MICS6814-RH2_OX)") (class "Default")
      (node (ref "MICS6814") (pin "K") (pinfunction "RH2_OX_K") (pintype "passive"))
      (node (ref "R11") (pin "1") (pinfunction "1_1") (pintype "passive"))
    )
    (net (code "25") (name "Net-(MICS6814-RH2_RED)") (class "Default")
      (node (ref "MICS6814") (pin "G") (pinfunction "RH2_RED_G") (pintype "passive"))
      (node (ref "R12") (pin "1") (pinfunction "1_1") (pintype "passive"))
    )
    (net (code "26") (name "Net-(MICS6814-RS2)") (class "Default")
      (node (ref "MICS6814") (pin "A") (pinfunction "RS2_A") (pintype "passive"))
      (node (ref "OPAMP") (pin "5") (pinfunction "IN2+_5") (pintype "input"))
    )
    (net (code "27") (name "Net-(MICS6814-RS2_RED)") (class "Default")
      (node (ref "MICS6814") (pin "H") (pinfunction "RS2_RED_H") (pintype "passive"))
      (node (ref "OPAMP") (pin "3") (pinfunction "IN1+_3") (pintype "input"))
    )
    (net (code "28") (name "Net-(OPAMP-IN1-)") (class "Default")
      (node (ref "OPAMP") (pin "1") (pinfunction "OUT1_1") (pintype "output"))
      (node (ref "OPAMP") (pin "2") (pinfunction "IN1-_2") (pintype "input"))
      (node (ref "R13") (pin "2") (pinfunction "2_2") (pintype "passive"))
    )
    (net (code "29") (name "Net-(OPAMP-IN2-)") (class "Default")
      (node (ref "OPAMP") (pin "6") (pinfunction "IN2-_6") (pintype "input"))
      (node (ref "OPAMP") (pin "7") (pinfunction "OUT2_7") (pintype "output"))
      (node (ref "R14") (pin "2") (pinfunction "2_2") (pintype "passive"))
    )
    (net (code "30") (name "Net-(VR_3.3-BYP)") (class "Default")
      (node (ref "C4") (pin "2") (pinfunction "2_2") (pintype "passive"))
      (node (ref "VR_3.3") (pin "4") (pinfunction "BYP_4") (pintype "passive"))
    )
    (net (code "31") (name "P8") (class "Default")
      (node (ref "MDBT42Q") (pin "4") (pinfunction "P0.27_4") (pintype "bidirectional"))
      (node (ref "R17") (pin "1") (pinfunction "1_1") (pintype "passive"))
    )
    (net (code "32") (name "SCL") (class "Default")
      (node (ref "BME280") (pin "4") (pinfunction "SCK_4") (pintype "input"))
      (node (ref "LIS3DH") (pin "4") (pinfunction "SCL/SPC_4") (pintype "bidirectional"))
      (node (ref "MDBT42Q") (pin "19") (pinfunction "P0.06_19") (pintype "bidirectional"))
      (node (ref "Q1") (pin "3") (pinfunction "D_3") (pintype "passive"))
      (node (ref "Q4") (pin "2") (pinfunction "S_2") (pintype "passive"))
      (node (ref "R4") (pin "2") (pinfunction "2_2") (pintype "passive"))
      (node (ref "R8") (pin "2") (pinfunction "2_2") (pintype "passive"))
      (node (ref "SCD41") (pin "9") (pinfunction "SCL_9") (pintype "bidirectional"))
    )
    (net (code "33") (name "SDA") (class "Default")
      (node (ref "BME280") (pin "3") (pinfunction "SDI_3") (pintype "bidirectional"))
      (node (ref "LIS3DH") (pin "6") (pinfunction "SDA/SDI/SDO_6") (pintype "bidirectional"))
      (node (ref "MDBT42Q") (pin "21") (pinfunction "P0.08_21") (pintype "bidirectional"))
      (node (ref "Q2") (pin "3") (pinfunction "D_3") (pintype "passive"))
      (node (ref "Q3") (pin "2") (pinfunction "S_2") (pintype "passive"))
      (node (ref "R10") (pin "1") (pinfunction "1_1") (pintype "passive"))
      (node (ref "R6") (pin "1") (pinfunction "1_1") (pintype "passive"))
      (node (ref "SCD41") (pin "10") (pinfunction "SDA_10") (pintype "bidirectional"))
    )
    (net (code "34") (name "SWDCLK") (class "Default")
      (node (ref "MDBT42Q") (pin "36") (pinfunction "SWDCLK_36") (pintype "input"))
      (node (ref "PROG") (pin "3") (pinfunction "3_3") (pintype "passive"))
    )
    (net (code "35") (name "SWDIO") (class "Default")
      (node (ref "MDBT42Q") (pin "37") (pinfunction "SWDIO_37") (pintype "bidirectional"))
      (node (ref "PROG") (pin "2") (pinfunction "2_2") (pintype "passive"))
    )
    (net (code "36") (name "VDD") (class "Default")
      (node (ref "C1") (pin "1") (pinfunction "1_1") (pintype "passive"))
      (node (ref "R19") (pin "2") (pinfunction "2_2") (pintype "passive"))
      (node (ref "S1") (pin "3") (pinfunction "3_3") (pintype "passive"))
      (node (ref "VR_3.3") (pin "1") (pinfunction "EN_1") (pintype "input"))
      (node (ref "VR_3.3") (pin "2") (pinfunction "IN_2") (pintype "power_in"))
      (node (ref "VR_5") (pin "2") (pinfunction "2_2") (pintype "passive"))
    )
    (net (code "37") (name "unconnected-(LIS3DH-1_NC-Pad2)") (class "Default")
      (node (ref "LIS3DH") (pin "2") (pinfunction "1_NC_2") (pintype "passive"))
    )
    (net (code "38") (name "unconnected-(LIS3DH-2_NC-Pad3)") (class "Default")
      (node (ref "LIS3DH") (pin "3") (pinfunction "2_NC_3") (pintype "passive"))
    )
    (net (code "39") (name "unconnected-(LIS3DH-ADC1-Pad16)") (class "Default")
      (node (ref "LIS3DH") (pin "16") (pinfunction "ADC1_16") (pintype "input"))
    )
    (net (code "40") (name "unconnected-(LIS3DH-ADC2-Pad15)") (class "Default")
      (node (ref "LIS3DH") (pin "15") (pinfunction "ADC2_15") (pintype "input"))
    )
    (net (code "41") (name "unconnected-(LIS3DH-ADC3-Pad13)") (class "Default")
      (node (ref "LIS3DH") (pin "13") (pinfunction "ADC3_13") (pintype "input"))
    )
    (net (code "42") (name "unconnected-(LIS3DH-INT1-Pad11)") (class "Default")
      (node (ref "LIS3DH") (pin "11") (pinfunction "INT1_11") (pintype "output"))
    )
    (net (code "43") (name "unconnected-(LIS3DH-INT2-Pad9)") (class "Default")
      (node (ref "LIS3DH") (pin "9") (pinfunction "INT2_9") (pintype "output"))
    )
    (net (code "44") (name "unconnected-(MDBT42Q-P0.02{slash}AIN0-Pad15)") (class "Default")
      (node (ref "MDBT42Q") (pin "15") (pinfunction "P0.02/AIN0_15") (pintype "bidirectional"))
    )
    (net (code "45") (name "unconnected-(MDBT42Q-P0.04{slash}AIN2-Pad17)") (class "Default")
      (node (ref "MDBT42Q") (pin "17") (pinfunction "P0.04/AIN2_17") (pintype "bidirectional"))
    )
    (net (code "46") (name "unconnected-(MDBT42Q-P0.07-Pad20)") (class "Default")
      (node (ref "MDBT42Q") (pin "20") (pinfunction "P0.07_20") (pintype "bidirectional"))
    )
    (net (code "47") (name "unconnected-(MDBT42Q-P0.09{slash}NFC1-Pad22)") (class "Default")
      (node (ref "MDBT42Q") (pin "22") (pinfunction "P0.09/NFC1_22") (pintype "bidirectional"))
    )
    (net (code "48") (name "unconnected-(MDBT42Q-P0.11-Pad25)") (class "Default")
      (node (ref "MDBT42Q") (pin "25") (pinfunction "P0.11_25") (pintype "bidirectional"))
    )
    (net (code "49") (name "unconnected-(MDBT42Q-P0.12-Pad26)") (class "Default")
      (node (ref "MDBT42Q") (pin "26") (pinfunction "P0.12_26") (pintype "bidirectional"))
    )
    (net (code "50") (name "unconnected-(MDBT42Q-P0.13-Pad27)") (class "Default")
      (node (ref "MDBT42Q") (pin "27") (pinfunction "P0.13_27") (pintype "bidirectional"))
    )
    (net (code "51") (name "unconnected-(MDBT42Q-P0.14{slash}TRACEDATA(3)-Pad28)") (class "Default")
      (node (ref "MDBT42Q") (pin "28") (pinfunction "P0.14/TRACEDATA(3)_28") (pintype "bidirectional"))
    )
    (net (code "52") (name "unconnected-(MDBT42Q-P0.15{slash}TRACEDATA(2)-Pad29)") (class "Default")
      (node (ref "MDBT42Q") (pin "29") (pinfunction "P0.15/TRACEDATA(2)_29") (pintype "bidirectional"))
    )
    (net (code "53") (name "unconnected-(MDBT42Q-P0.16{slash}TRACEDATA(1)-Pad30)") (class "Default")
      (node (ref "MDBT42Q") (pin "30") (pinfunction "P0.16/TRACEDATA(1)_30") (pintype "bidirectional"))
    )
    (net (code "54") (name "unconnected-(MDBT42Q-P0.17-Pad31)") (class "Default")
      (node (ref "MDBT42Q") (pin "31") (pinfunction "P0.17_31") (pintype "bidirectional"))
    )
    (net (code "55") (name "unconnected-(MDBT42Q-P0.18{slash}TRACEDATA(0)-Pad32)") (class "Default")
      (node (ref "MDBT42Q") (pin "32") (pinfunction "P0.18/TRACEDATA(0)_32") (pintype "bidirectional"))
    )
    (net (code "56") (name "unconnected-(MDBT42Q-P0.19-Pad33)") (class "Default")
      (node (ref "MDBT42Q") (pin "33") (pinfunction "P0.19_33") (pintype "bidirectional"))
    )
    (net (code "57") (name "unconnected-(MDBT42Q-P0.20{slash}TRACECLK-Pad34)") (class "Default")
      (node (ref "MDBT42Q") (pin "34") (pinfunction "P0.20/TRACECLK_34") (pintype "bidirectional"))
    )
    (net (code "58") (name "unconnected-(MDBT42Q-P0.21{slash}RESET-Pad35)") (class "Default")
      (node (ref "MDBT42Q") (pin "35") (pinfunction "P0.21/RESET_35") (pintype "bidirectional"))
    )
    (net (code "59") (name "unconnected-(MDBT42Q-P0.22-Pad38)") (class "Default")
      (node (ref "MDBT42Q") (pin "38") (pinfunction "P0.22_38") (pintype "bidirectional"))
    )
    (net (code "60") (name "unconnected-(MDBT42Q-P0.23-Pad41)") (class "Default")
      (node (ref "MDBT42Q") (pin "41") (pinfunction "P0.23_41") (pintype "bidirectional"))
    )
    (net (code "61") (name "unconnected-(MDBT42Q-P0.24-Pad40)") (class "Default")
      (node (ref "MDBT42Q") (pin "40") (pinfunction "P0.24_40") (pintype "bidirectional"))
    )
    (net (code "62") (name "unconnected-(MDBT42Q-P0.25-Pad2)") (class "Default")
      (node (ref "MDBT42Q") (pin "2") (pinfunction "P0.25_2") (pintype "bidirectional"))
    )
    (net (code "63") (name "unconnected-(MDBT42Q-P0.26-Pad3)") (class "Default")
      (node (ref "MDBT42Q") (pin "3") (pinfunction "P0.26_3") (pintype "bidirectional"))
    )
    (net (code "64") (name "unconnected-(MDBT42Q-P0.28{slash}AIN4-Pad5)") (class "Default")
      (node (ref "MDBT42Q") (pin "5") (pinfunction "P0.28/AIN4_5") (pintype "bidirectional"))
    )
    (net (code "65") (name "unconnected-(MDBT42Q-P0.29{slash}AIN5-Pad6)") (class "Default")
      (node (ref "MDBT42Q") (pin "6") (pinfunction "P0.29/AIN5_6") (pintype "bidirectional"))
    )
    (net (code "66") (name "unconnected-(MDBT42Q-P0.30AIN6-Pad7)") (class "Default")
      (node (ref "MDBT42Q") (pin "7") (pinfunction "P0.30AIN6_7") (pintype "bidirectional"))
    )
    (net (code "67") (name "unconnected-(MICS6814-RH1_NH3-PadC)") (class "Default")
      (node (ref "MICS6814") (pin "C") (pinfunction "RH1_NH3_C") (pintype "passive"))
    )
    (net (code "68") (name "unconnected-(MICS6814-RH2_NH3-PadE)") (class "Default")
      (node (ref "MICS6814") (pin "E") (pinfunction "RH2_NH3_E") (pintype "passive"))
    )
    (net (code "69") (name "unconnected-(MICS6814-RS1_NH3-PadD)") (class "Default")
      (node (ref "MICS6814") (pin "D") (pinfunction "RS1_NH3_D") (pintype "passive"))
    )
    (net (code "70") (name "unconnected-(MICS6814-RS2_NH3-PadF)") (class "Default")
      (node (ref "MICS6814") (pin "F") (pinfunction "RS2_NH3_F") (pintype "passive"))
    )
    (net (code "71") (name "unconnected-(S1-Pad1)") (class "Default")
      (node (ref "S1") (pin "1") (pinfunction "1_1") (pintype "passive"))
    )
    (net (code "72") (name "unconnected-(SCD41-DNC_1-Pad1)") (class "Default")
      (node (ref "SCD41") (pin "1") (pinfunction "DNC_1_1") (pintype "bidirectional"))
    )
    (net (code "73") (name "unconnected-(SCD41-DNC_2-Pad2)") (class "Default")
      (node (ref "SCD41") (pin "2") (pinfunction "DNC_2_2") (pintype "bidirectional"))
    )
    (net (code "74") (name "unconnected-(SCD41-DNC_3-Pad3)") (class "Default")
      (node (ref "SCD41") (pin "3") (pinfunction "DNC_3_3") (pintype "bidirectional"))
    )
    (net (code "75") (name "unconnected-(SCD41-DNC_4-Pad4)") (class "Default")
      (node (ref "SCD41") (pin "4") (pinfunction "DNC_4_4") (pintype "bidirectional"))
    )
    (net (code "76") (name "unconnected-(SCD41-DNC_5-Pad5)") (class "Default")
      (node (ref "SCD41") (pin "5") (pinfunction "DNC_5_5") (pintype "bidirectional"))
    )
    (net (code "77") (name "unconnected-(SCD41-DNC_6-Pad8)") (class "Default")
      (node (ref "SCD41") (pin "8") (pinfunction "DNC_6_8") (pintype "bidirectional"))
    )
    (net (code "78") (name "unconnected-(SCD41-DNC_7-Pad11)") (class "Default")
      (node (ref "SCD41") (pin "11") (pinfunction "DNC_7_11") (pintype "bidirectional"))
    )
    (net (code "79") (name "unconnected-(SCD41-DNC_8-Pad12)") (class "Default")
      (node (ref "SCD41") (pin "12") (pinfunction "DNC_8_12") (pintype "bidirectional"))
    )
    (net (code "80") (name "unconnected-(SCD41-DNC_9-Pad13)") (class "Default")
      (node (ref "SCD41") (pin "13") (pinfunction "DNC_9_13") (pintype "bidirectional"))
    )
    (net (code "81") (name "unconnected-(SCD41-DNC_10-Pad14)") (class "Default")
      (node (ref "SCD41") (pin "14") (pinfunction "DNC_10_14") (pintype "bidirectional"))
    )
    (net (code "82") (name "unconnected-(SCD41-DNC_11-Pad15)") (class "Default")
      (node (ref "SCD41") (pin "15") (pinfunction "DNC_11_15") (pintype "bidirectional"))
    )
    (net (code "83") (name "unconnected-(SCD41-DNC_12-Pad16)") (class "Default")
      (node (ref "SCD41") (pin "16") (pinfunction "DNC_12_16") (pintype "bidirectional"))
    )
    (net (code "84") (name "unconnected-(SCD41-DNC_13-Pad17)") (class "Default")
      (node (ref "SCD41") (pin "17") (pinfunction "DNC_13_17") (pintype "bidirectional"))
    )
    (net (code "85") (name "unconnected-(SCD41-DNC_14-Pad18)") (class "Default")
      (node (ref "SCD41") (pin "18") (pinfunction "DNC_14_18") (pintype "bidirectional"))
    )
    (net (code "86") (name "unconnected-(VR_1.8-NC-Pad4)") (class "Default")
      (node (ref "VR_1.8") (pin "4") (pinfunction "NC_4") (pintype "no_connect"))
    )
    (net (code "87") (name "unconnected-(VR_5-Pad4)") (class "Default")
      (node (ref "VR_5") (pin "4") (pinfunction "4_4") (pintype "passive"))
    )
    (net (code "88") (name "unconnected-(VR_5-Pad5)") (class "Default")
      (node (ref "VR_5") (pin "5") (pinfunction "5_5") (pintype "passive"))
    )
  )
)
